# 03_mcu.net
KiCad netlist of a schematic drawn in Altium Designer
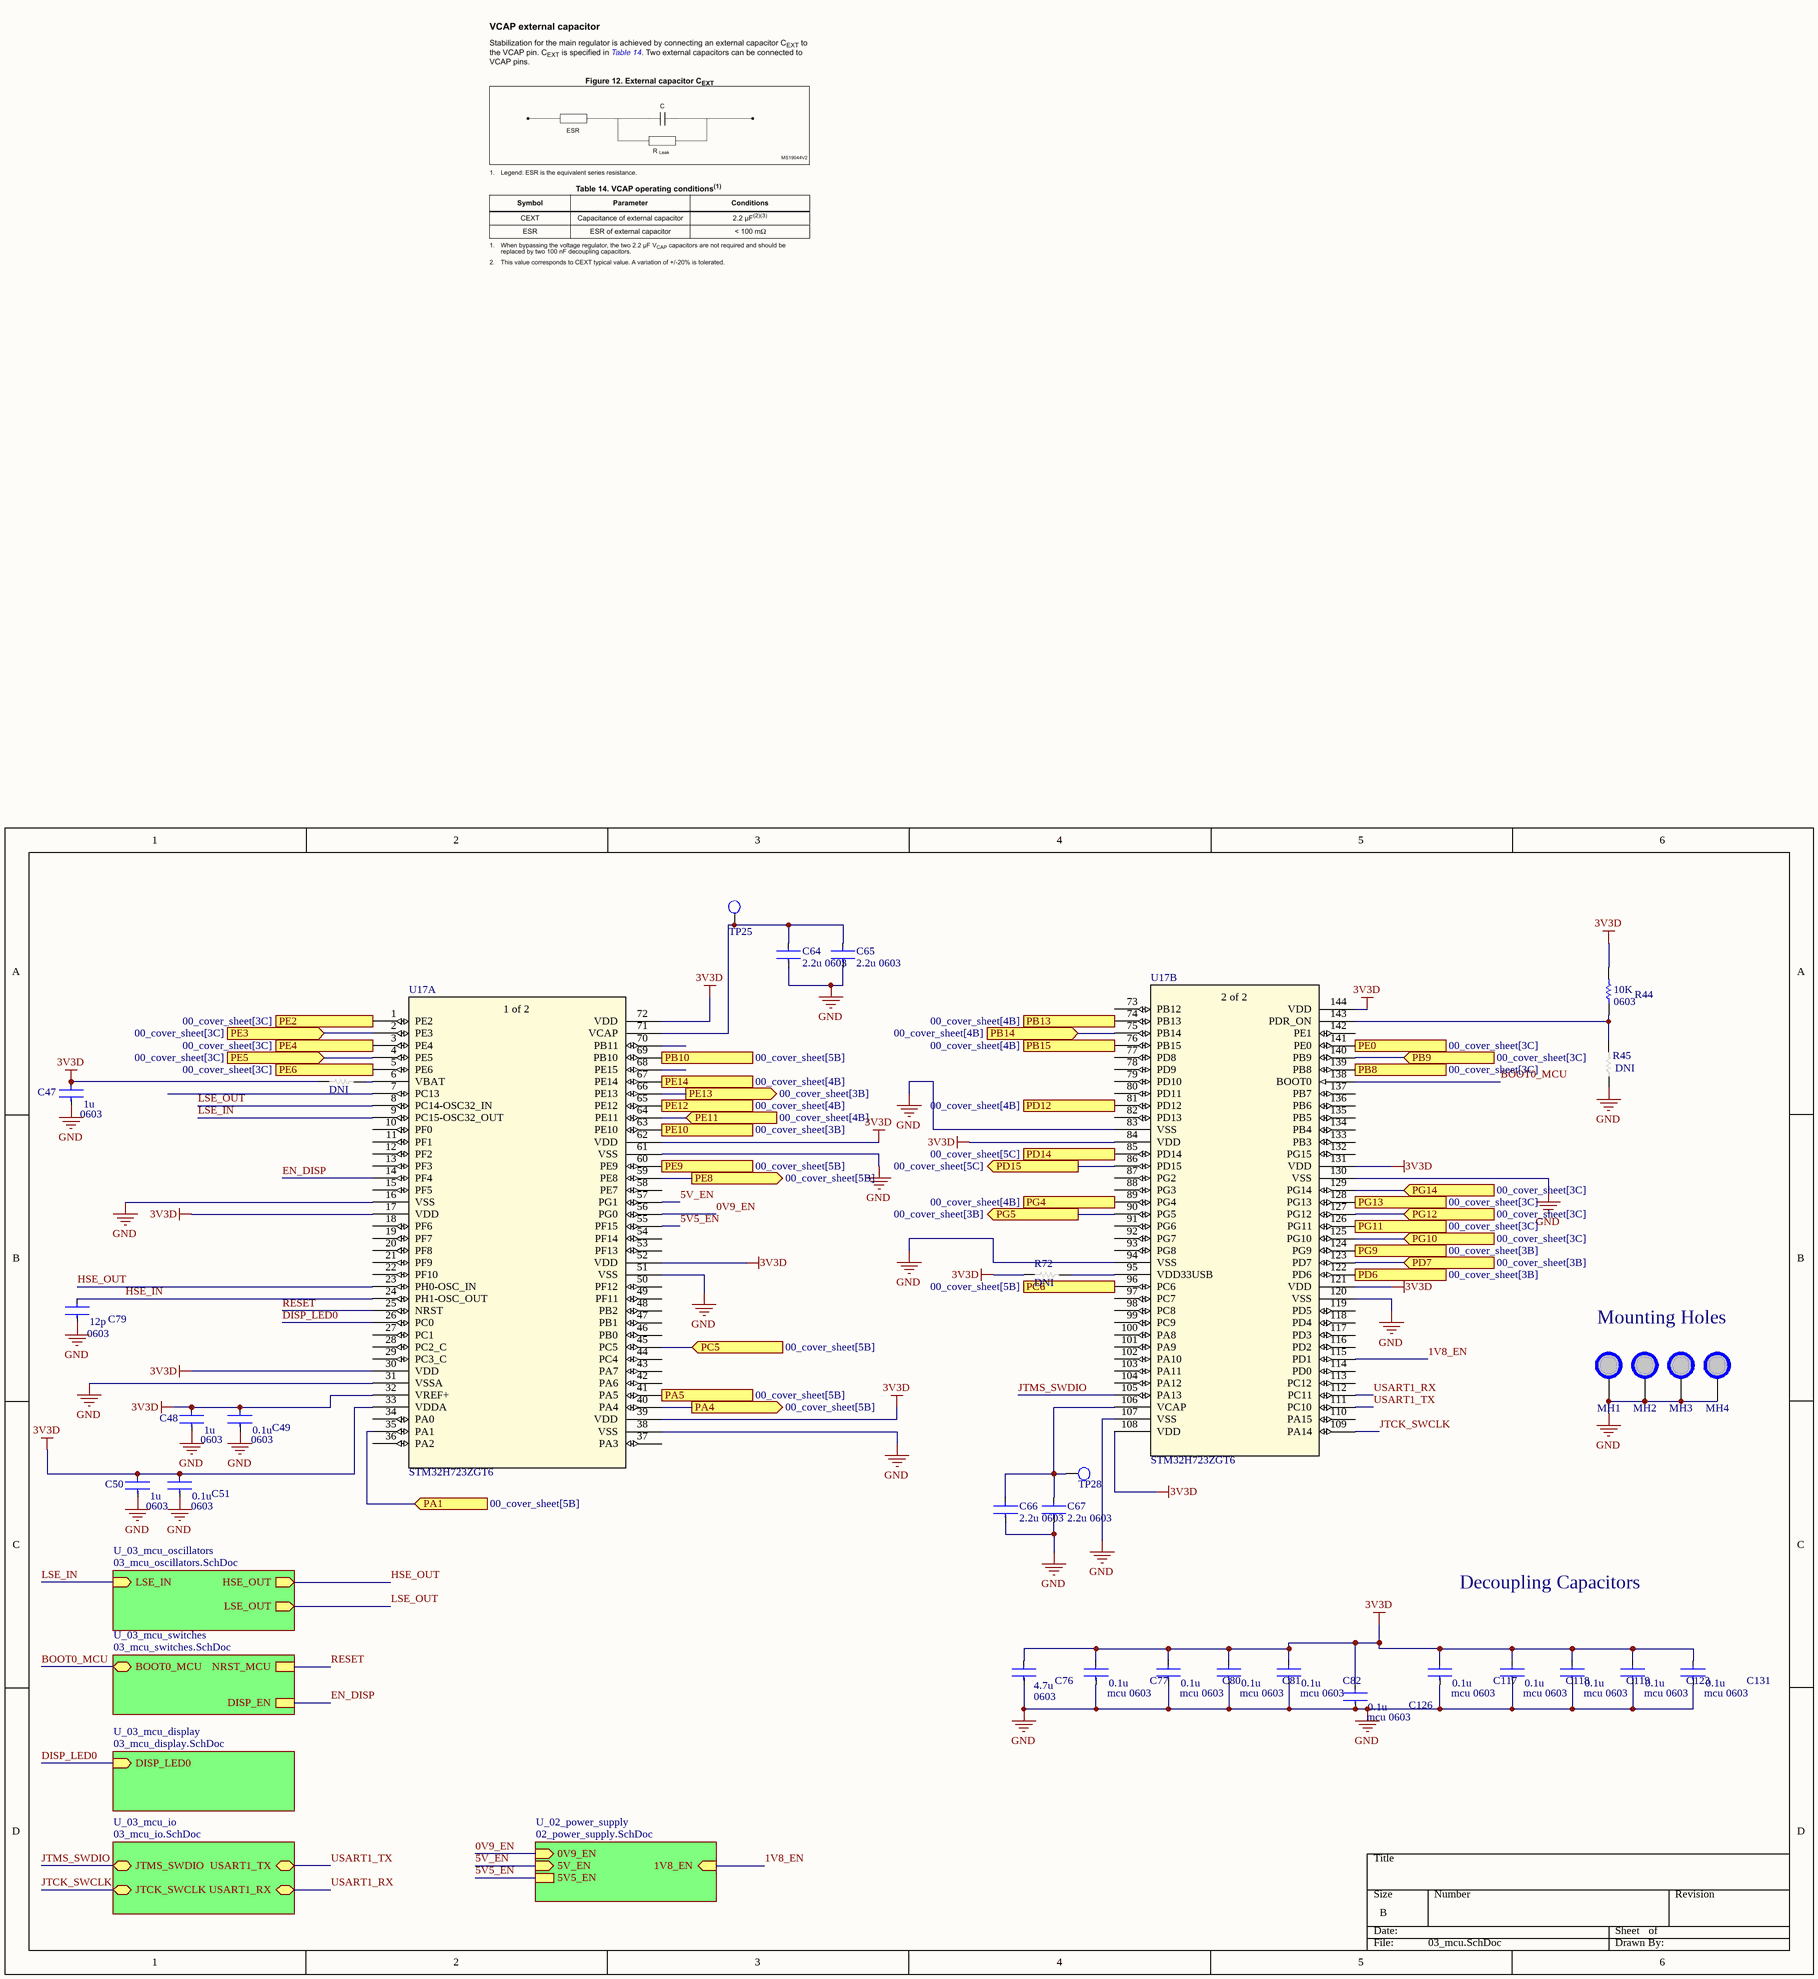
[diagram p0: 03_mcu.SchDoc]

(export (version "E")
  (design (tool "Eeschema 10.0.6"))
  (components
    (comp (ref "C47")
      (value "C1608X5R1E105K080AC")
      (footprint "CAPTDK0603")
      (description "CAP CER 1UF 25V X5R 0603")
      (libsource (lib "tcspc00") (part "C1608X5R1E105K080AC"))
    )
    (comp (ref "C48")
      (value "C1608X5R1E105K080AC")
      (footprint "CAPTDK0603")
      (description "CAP CER 1UF 25V X5R 0603")
      (libsource (lib "tcspc00") (part "C1608X5R1E105K080AC"))
    )
    (comp (ref "C49")
      (value "CGA3E2X7R1H104K080AA")
      (footprint "CAPTDK0603")
      (description "CAP CER 0.1UF 50V X7R 0603")
      (libsource (lib "tcspc00") (part "CGA3E2X7R1H104K080AA"))
    )
    (comp (ref "C50")
      (value "C1608X5R1E105K080AC")
      (footprint "CAPTDK0603")
      (description "CAP CER 1UF 25V X5R 0603")
      (libsource (lib "tcspc00") (part "C1608X5R1E105K080AC"))
    )
    (comp (ref "C51")
      (value "CGA3E2X7R1H104K080AA")
      (footprint "CAPTDK0603")
      (description "CAP CER 0.1UF 50V X7R 0603")
      (libsource (lib "tcspc00") (part "CGA3E2X7R1H104K080AA"))
    )
    (comp (ref "C64")
      (value "2.2u 0603")
      (footprint "CAPTDK0603")
      (description "CAP CER 2.2UF 25V X5R 0603")
      (libsource (lib "tcspc00") (part "C1608X5R1E225K080AB"))
    )
    (comp (ref "C65")
      (value "2.2u 0603")
      (footprint "CAPTDK0603")
      (description "CAP CER 2.2UF 25V X5R 0603")
      (libsource (lib "tcspc00") (part "C1608X5R1E225K080AB"))
    )
    (comp (ref "C66")
      (value "2.2u 0603")
      (footprint "CAPTDK0603")
      (description "CAP CER 2.2UF 25V X5R 0603")
      (libsource (lib "tcspc00") (part "C1608X5R1E225K080AB"))
    )
    (comp (ref "C67")
      (value "2.2u 0603")
      (footprint "CAPTDK0603")
      (description "CAP CER 2.2UF 25V X5R 0603")
      (libsource (lib "tcspc00") (part "C1608X5R1E225K080AB"))
    )
    (comp (ref "C76")
      (value "C1608X5R1E475K080AC")
      (footprint "CAPTDK0603")
      (description "CAP CER 4.7UF 25V X5R 0603")
      (libsource (lib "tcspc00") (part "C1608X5R1E475K080AC"))
    )
    (comp (ref "C77")
      (value "NMC0603X7R104K50TRPF")
      (footprint "CAPTDK0603")
      (description "0.1 µF ±10% 50V Ceramic Capacitor X7R 0603 (1608 Metric) low esr mcu caps")
      (libsource (lib "tcspc00") (part "NMC0603X7R104K50TRPF"))
    )
    (comp (ref "C79")
      (value "CGA3E2C0G1H120J080AA")
      (footprint "CAPTDK0603")
      (description "CAP CER 12PF 50V C0G 0603")
      (libsource (lib "tcspc00") (part "CGA3E2C0G1H120J080AA"))
    )
    (comp (ref "C80")
      (value "NMC0603X7R104K50TRPF")
      (footprint "CAPTDK0603")
      (description "0.1 µF ±10% 50V Ceramic Capacitor X7R 0603 (1608 Metric) low esr mcu caps")
      (libsource (lib "tcspc00") (part "NMC0603X7R104K50TRPF"))
    )
    (comp (ref "C81")
      (value "NMC0603X7R104K50TRPF")
      (footprint "CAPTDK0603")
      (description "0.1 µF ±10% 50V Ceramic Capacitor X7R 0603 (1608 Metric) low esr mcu caps")
      (libsource (lib "tcspc00") (part "NMC0603X7R104K50TRPF"))
    )
    (comp (ref "C82")
      (value "NMC0603X7R104K50TRPF")
      (footprint "CAPTDK0603")
      (description "0.1 µF ±10% 50V Ceramic Capacitor X7R 0603 (1608 Metric) low esr mcu caps")
      (libsource (lib "tcspc00") (part "NMC0603X7R104K50TRPF"))
    )
    (comp (ref "C117")
      (value "NMC0603X7R104K50TRPF")
      (footprint "CAPTDK0603")
      (description "0.1 µF ±10% 50V Ceramic Capacitor X7R 0603 (1608 Metric) low esr mcu caps")
      (libsource (lib "tcspc00") (part "NMC0603X7R104K50TRPF"))
    )
    (comp (ref "C118")
      (value "NMC0603X7R104K50TRPF")
      (footprint "CAPTDK0603")
      (description "0.1 µF ±10% 50V Ceramic Capacitor X7R 0603 (1608 Metric) low esr mcu caps")
      (libsource (lib "tcspc00") (part "NMC0603X7R104K50TRPF"))
    )
    (comp (ref "C119")
      (value "NMC0603X7R104K50TRPF")
      (footprint "CAPTDK0603")
      (description "0.1 µF ±10% 50V Ceramic Capacitor X7R 0603 (1608 Metric) low esr mcu caps")
      (libsource (lib "tcspc00") (part "NMC0603X7R104K50TRPF"))
    )
    (comp (ref "C123")
      (value "NMC0603X7R104K50TRPF")
      (footprint "CAPTDK0603")
      (description "0.1 µF ±10% 50V Ceramic Capacitor X7R 0603 (1608 Metric) low esr mcu caps")
      (libsource (lib "tcspc00") (part "NMC0603X7R104K50TRPF"))
    )
    (comp (ref "C126")
      (value "NMC0603X7R104K50TRPF")
      (footprint "CAPTDK0603")
      (description "0.1 µF ±10% 50V Ceramic Capacitor X7R 0603 (1608 Metric) low esr mcu caps")
      (libsource (lib "tcspc00") (part "NMC0603X7R104K50TRPF"))
    )
    (comp (ref "C131")
      (value "NMC0603X7R104K50TRPF")
      (footprint "CAPTDK0603")
      (description "0.1 µF ±10% 50V Ceramic Capacitor X7R 0603 (1608 Metric) low esr mcu caps")
      (libsource (lib "tcspc00") (part "NMC0603X7R104K50TRPF"))
    )
    (comp (ref "MH1")
      (value "M3.5 Mounting Hole")
      (footprint "M3.5 Mounting Hole - Supported")
      (fields (field (name "PUBLISHER") "Altium Limited"))
      (libsource (lib "tcspc00") (part "M3.5 Mounting Hole"))
    )
    (comp (ref "MH2")
      (value "M3.5 Mounting Hole")
      (footprint "M3.5 Mounting Hole - Supported")
      (fields (field (name "PUBLISHER") "Altium Limited"))
      (libsource (lib "tcspc00") (part "M3.5 Mounting Hole"))
    )
    (comp (ref "MH3")
      (value "M3.5 Mounting Hole")
      (footprint "M3.5 Mounting Hole - Supported")
      (fields (field (name "PUBLISHER") "Altium Limited"))
      (libsource (lib "tcspc00") (part "M3.5 Mounting Hole"))
    )
    (comp (ref "MH4")
      (value "M3.5 Mounting Hole")
      (footprint "M3.5 Mounting Hole - Supported")
      (fields (field (name "PUBLISHER") "Altium Limited"))
      (libsource (lib "tcspc00") (part "M3.5 Mounting Hole"))
    )
    (comp (ref "R44")
      (value "RMCF0603JG10K0")
      (footprint "RES-STACK-POLE-0603")
      (description "RES 10K OHM 5% 1/10W 0603")
      (libsource (lib "tcspc00") (part "RMCF0603JG10K0"))
    )
    (comp (ref "R45")
      (value "DNI")
      (footprint "RES_0603")
      (description "RES DNI 0603")
      (libsource (lib "tcspc00") (part "R0603"))
    )
    (comp (ref "R46")
      (value "DNI")
      (footprint "RES_0603")
      (description "RES DNI 0603")
      (libsource (lib "tcspc00") (part "R0603"))
    )
    (comp (ref "R72")
      (value "DNI")
      (footprint "RES_0603")
      (description "RES DNI 0603")
      (libsource (lib "tcspc00") (part "R0603"))
    )
    (comp (ref "TP25")
      (value "TESTPOINT_S")
      (footprint "TESTPOINT_S")
      (description "Testpoint Surface Pad")
      (libsource (lib "Schlib1") (part "TESTPOINT_S"))
    )
    (comp (ref "TP28")
      (value "TESTPOINT_S")
      (footprint "TESTPOINT_S")
      (description "Testpoint Surface Pad")
      (libsource (lib "Schlib1") (part "TESTPOINT_S"))
    )
    (comp (ref "U17")
      (value "STM32H723ZGT6")
      (footprint "LQFP144")
      (description "No Description Available")
      (fields (field (name "COPYRIGHT") "Copyright (C) 2024 Ultra Librarian. All rights reserved."))
      (libsource (lib "tcspc00") (part "STM32H723ZGT6"))
    )
  )
  (nets
    (net (code "1") (name "/0V9_EN") (class "Default")
      (node (ref "U17") (pin "56") (pinfunction "PG0_56") (pintype "bidirectional"))
    )
    (net (code "2") (name "/1V8_EN") (class "Default")
      (node (ref "U17") (pin "115") (pinfunction "PD1_115") (pintype "bidirectional"))
    )
    (net (code "3") (name "/5V5_EN") (class "Default")
      (node (ref "U17") (pin "55") (pinfunction "PF15_55") (pintype "bidirectional"))
    )
    (net (code "4") (name "/5V_EN") (class "Default")
      (node (ref "U17") (pin "57") (pinfunction "PG1_57") (pintype "bidirectional"))
    )
    (net (code "5") (name "/BOOT0_MCU") (class "Default")
      (node (ref "U17") (pin "138") (pinfunction "BOOT0_138") (pintype "input"))
    )
    (net (code "6") (name "/DISP_LED0") (class "Default")
      (node (ref "U17") (pin "26") (pinfunction "PC0_26") (pintype "bidirectional"))
    )
    (net (code "7") (name "/EN_DISP") (class "Default")
      (node (ref "U17") (pin "14") (pinfunction "PF4_14") (pintype "bidirectional"))
    )
    (net (code "8") (name "/HSE_IN") (class "Default")
      (node (ref "C79") (pin "1") (pinfunction "1_1") (pintype "passive"))
      (node (ref "U17") (pin "24") (pinfunction "PH1-OSC_OUT_24") (pintype "bidirectional"))
    )
    (net (code "9") (name "/HSE_OUT") (class "Default")
      (node (ref "U17") (pin "23") (pinfunction "PH0-OSC_IN_23") (pintype "bidirectional"))
    )
    (net (code "10") (name "/JTCK_SWCLK") (class "Default")
      (node (ref "U17") (pin "109") (pinfunction "PA14_109") (pintype "bidirectional"))
    )
    (net (code "11") (name "/JTMS_SWDIO") (class "Default")
      (node (ref "U17") (pin "105") (pinfunction "PA13_105") (pintype "bidirectional"))
    )
    (net (code "12") (name "/LSE_IN") (class "Default")
      (node (ref "U17") (pin "9") (pinfunction "PC15-OSC32_OUT_9") (pintype "bidirectional"))
    )
    (net (code "13") (name "/LSE_OUT") (class "Default")
      (node (ref "U17") (pin "8") (pinfunction "PC14-OSC32_IN_8") (pintype "bidirectional"))
    )
    (net (code "14") (name "/PA1") (class "Default")
      (node (ref "U17") (pin "35") (pinfunction "PA1_35") (pintype "bidirectional"))
    )
    (net (code "15") (name "/PA4") (class "Default")
      (node (ref "U17") (pin "40") (pinfunction "PA4_40") (pintype "bidirectional"))
    )
    (net (code "16") (name "/PA5") (class "Default")
      (node (ref "U17") (pin "41") (pinfunction "PA5_41") (pintype "bidirectional"))
    )
    (net (code "17") (name "/PB8") (class "Default")
      (node (ref "U17") (pin "139") (pinfunction "PB8_139") (pintype "bidirectional"))
    )
    (net (code "18") (name "/PB9") (class "Default")
      (node (ref "U17") (pin "140") (pinfunction "PB9_140") (pintype "bidirectional"))
    )
    (net (code "19") (name "/PB10") (class "Default")
      (node (ref "U17") (pin "69") (pinfunction "PB10_69") (pintype "bidirectional"))
    )
    (net (code "20") (name "/PB13") (class "Default")
      (node (ref "U17") (pin "74") (pinfunction "PB13_74") (pintype "bidirectional"))
    )
    (net (code "21") (name "/PB14") (class "Default")
      (node (ref "U17") (pin "75") (pinfunction "PB14_75") (pintype "bidirectional"))
    )
    (net (code "22") (name "/PB15") (class "Default")
      (node (ref "U17") (pin "76") (pinfunction "PB15_76") (pintype "bidirectional"))
    )
    (net (code "23") (name "/PC5") (class "Default")
      (node (ref "U17") (pin "45") (pinfunction "PC5_45") (pintype "bidirectional"))
    )
    (net (code "24") (name "/PC6") (class "Default")
      (node (ref "U17") (pin "96") (pinfunction "PC6_96") (pintype "bidirectional"))
    )
    (net (code "25") (name "/PD6") (class "Default")
      (node (ref "U17") (pin "122") (pinfunction "PD6_122") (pintype "bidirectional"))
    )
    (net (code "26") (name "/PD7") (class "Default")
      (node (ref "U17") (pin "123") (pinfunction "PD7_123") (pintype "bidirectional"))
    )
    (net (code "27") (name "/PD12") (class "Default")
      (node (ref "U17") (pin "81") (pinfunction "PD12_81") (pintype "bidirectional"))
    )
    (net (code "28") (name "/PD14") (class "Default")
      (node (ref "U17") (pin "85") (pinfunction "PD14_85") (pintype "bidirectional"))
    )
    (net (code "29") (name "/PD15") (class "Default")
      (node (ref "U17") (pin "86") (pinfunction "PD15_86") (pintype "bidirectional"))
    )
    (net (code "30") (name "/PE0") (class "Default")
      (node (ref "U17") (pin "141") (pinfunction "PE0_141") (pintype "bidirectional"))
    )
    (net (code "31") (name "/PE2") (class "Default")
      (node (ref "U17") (pin "1") (pinfunction "PE2_1") (pintype "bidirectional"))
    )
    (net (code "32") (name "/PE3") (class "Default")
      (node (ref "U17") (pin "2") (pinfunction "PE3_2") (pintype "bidirectional"))
    )
    (net (code "33") (name "/PE4") (class "Default")
      (node (ref "U17") (pin "3") (pinfunction "PE4_3") (pintype "bidirectional"))
    )
    (net (code "34") (name "/PE5") (class "Default")
      (node (ref "U17") (pin "4") (pinfunction "PE5_4") (pintype "bidirectional"))
    )
    (net (code "35") (name "/PE6") (class "Default")
      (node (ref "U17") (pin "5") (pinfunction "PE6_5") (pintype "bidirectional"))
    )
    (net (code "36") (name "/PE8") (class "Default")
      (node (ref "U17") (pin "59") (pinfunction "PE8_59") (pintype "bidirectional"))
    )
    (net (code "37") (name "/PE9") (class "Default")
      (node (ref "U17") (pin "60") (pinfunction "PE9_60") (pintype "bidirectional"))
    )
    (net (code "38") (name "/PE10") (class "Default")
      (node (ref "U17") (pin "63") (pinfunction "PE10_63") (pintype "bidirectional"))
    )
    (net (code "39") (name "/PE11") (class "Default")
      (node (ref "U17") (pin "64") (pinfunction "PE11_64") (pintype "bidirectional"))
    )
    (net (code "40") (name "/PE12") (class "Default")
      (node (ref "U17") (pin "65") (pinfunction "PE12_65") (pintype "bidirectional"))
    )
    (net (code "41") (name "/PE13") (class "Default")
      (node (ref "U17") (pin "66") (pinfunction "PE13_66") (pintype "bidirectional"))
    )
    (net (code "42") (name "/PE14") (class "Default")
      (node (ref "U17") (pin "67") (pinfunction "PE14_67") (pintype "bidirectional"))
    )
    (net (code "43") (name "/PG4") (class "Default")
      (node (ref "U17") (pin "89") (pinfunction "PG4_89") (pintype "bidirectional"))
    )
    (net (code "44") (name "/PG5") (class "Default")
      (node (ref "U17") (pin "90") (pinfunction "PG5_90") (pintype "bidirectional"))
    )
    (net (code "45") (name "/PG9") (class "Default")
      (node (ref "U17") (pin "124") (pinfunction "PG9_124") (pintype "bidirectional"))
    )
    (net (code "46") (name "/PG10") (class "Default")
      (node (ref "U17") (pin "125") (pinfunction "PG10_125") (pintype "bidirectional"))
    )
    (net (code "47") (name "/PG11") (class "Default")
      (node (ref "U17") (pin "126") (pinfunction "PG11_126") (pintype "bidirectional"))
    )
    (net (code "48") (name "/PG12") (class "Default")
      (node (ref "U17") (pin "127") (pinfunction "PG12_127") (pintype "bidirectional"))
    )
    (net (code "49") (name "/PG13") (class "Default")
      (node (ref "U17") (pin "128") (pinfunction "PG13_128") (pintype "bidirectional"))
    )
    (net (code "50") (name "/PG14") (class "Default")
      (node (ref "U17") (pin "129") (pinfunction "PG14_129") (pintype "bidirectional"))
    )
    (net (code "51") (name "/RESET") (class "Default")
      (node (ref "U17") (pin "25") (pinfunction "NRST_25") (pintype "bidirectional"))
    )
    (net (code "52") (name "/USART1_RX") (class "Default")
      (node (ref "U17") (pin "112") (pinfunction "PC11_112") (pintype "bidirectional"))
    )
    (net (code "53") (name "/USART1_TX") (class "Default")
      (node (ref "U17") (pin "111") (pinfunction "PC10_111") (pintype "bidirectional"))
    )
    (net (code "54") (name "3V3D") (class "Default")
      (node (ref "C117") (pin "1") (pinfunction "1_1") (pintype "passive"))
      (node (ref "C118") (pin "1") (pinfunction "1_1") (pintype "passive"))
      (node (ref "C119") (pin "1") (pinfunction "1_1") (pintype "passive"))
      (node (ref "C123") (pin "1") (pinfunction "1_1") (pintype "passive"))
      (node (ref "C126") (pin "1") (pinfunction "1_1") (pintype "passive"))
      (node (ref "C131") (pin "1") (pinfunction "1_1") (pintype "passive"))
      (node (ref "C47") (pin "1") (pinfunction "1_1") (pintype "passive"))
      (node (ref "C48") (pin "1") (pinfunction "1_1") (pintype "passive"))
      (node (ref "C49") (pin "1") (pinfunction "1_1") (pintype "passive"))
      (node (ref "C50") (pin "1") (pinfunction "1_1") (pintype "passive"))
      (node (ref "C51") (pin "1") (pinfunction "1_1") (pintype "passive"))
      (node (ref "C76") (pin "1") (pinfunction "1_1") (pintype "passive"))
      (node (ref "C77") (pin "1") (pinfunction "1_1") (pintype "passive"))
      (node (ref "C80") (pin "1") (pinfunction "1_1") (pintype "passive"))
      (node (ref "C81") (pin "1") (pinfunction "1_1") (pintype "passive"))
      (node (ref "C82") (pin "1") (pinfunction "1_1") (pintype "passive"))
      (node (ref "R44") (pin "2") (pinfunction "2_2") (pintype "passive"))
      (node (ref "R46") (pin "1") (pinfunction "1_1") (pintype "passive"))
      (node (ref "R72") (pin "1") (pinfunction "1_1") (pintype "passive"))
      (node (ref "U17") (pin "108") (pinfunction "VDD_108") (pintype "power_in"))
      (node (ref "U17") (pin "121") (pinfunction "VDD_121") (pintype "power_in"))
      (node (ref "U17") (pin "131") (pinfunction "VDD_131") (pintype "power_in"))
      (node (ref "U17") (pin "144") (pinfunction "VDD_144") (pintype "power_in"))
      (node (ref "U17") (pin "17") (pinfunction "VDD_17") (pintype "power_in"))
      (node (ref "U17") (pin "30") (pinfunction "VDD_30") (pintype "power_in"))
      (node (ref "U17") (pin "32") (pinfunction "VREF+_32") (pintype "power_in"))
      (node (ref "U17") (pin "33") (pinfunction "VDDA_33") (pintype "power_in"))
      (node (ref "U17") (pin "39") (pinfunction "VDD_39") (pintype "power_in"))
      (node (ref "U17") (pin "52") (pinfunction "VDD_52") (pintype "power_in"))
      (node (ref "U17") (pin "62") (pinfunction "VDD_62") (pintype "power_in"))
      (node (ref "U17") (pin "72") (pinfunction "VDD_72") (pintype "power_in"))
      (node (ref "U17") (pin "84") (pinfunction "VDD_84") (pintype "power_in"))
    )
    (net (code "55") (name "GND") (class "Default")
      (node (ref "C117") (pin "2") (pinfunction "2_2") (pintype "passive"))
      (node (ref "C118") (pin "2") (pinfunction "2_2") (pintype "passive"))
      (node (ref "C119") (pin "2") (pinfunction "2_2") (pintype "passive"))
      (node (ref "C123") (pin "2") (pinfunction "2_2") (pintype "passive"))
      (node (ref "C126") (pin "2") (pinfunction "2_2") (pintype "passive"))
      (node (ref "C131") (pin "2") (pinfunction "2_2") (pintype "passive"))
      (node (ref "C47") (pin "2") (pinfunction "2_2") (pintype "passive"))
      (node (ref "C48") (pin "2") (pinfunction "2_2") (pintype "passive"))
      (node (ref "C49") (pin "2") (pinfunction "2_2") (pintype "passive"))
      (node (ref "C50") (pin "2") (pinfunction "2_2") (pintype "passive"))
      (node (ref "C51") (pin "2") (pinfunction "2_2") (pintype "passive"))
      (node (ref "C64") (pin "2") (pinfunction "2_2") (pintype "passive"))
      (node (ref "C65") (pin "2") (pinfunction "2_2") (pintype "passive"))
      (node (ref "C66") (pin "2") (pinfunction "2_2") (pintype "passive"))
      (node (ref "C67") (pin "2") (pinfunction "2_2") (pintype "passive"))
      (node (ref "C76") (pin "2") (pinfunction "2_2") (pintype "passive"))
      (node (ref "C77") (pin "2") (pinfunction "2_2") (pintype "passive"))
      (node (ref "C79") (pin "2") (pinfunction "2_2") (pintype "passive"))
      (node (ref "C80") (pin "2") (pinfunction "2_2") (pintype "passive"))
      (node (ref "C81") (pin "2") (pinfunction "2_2") (pintype "passive"))
      (node (ref "C82") (pin "2") (pinfunction "2_2") (pintype "passive"))
      (node (ref "MH1") (pin "1") (pinfunction "1_1") (pintype "passive"))
      (node (ref "MH2") (pin "1") (pinfunction "1_1") (pintype "passive"))
      (node (ref "MH3") (pin "1") (pinfunction "1_1") (pintype "passive"))
      (node (ref "MH4") (pin "1") (pinfunction "1_1") (pintype "passive"))
      (node (ref "R45") (pin "1") (pinfunction "1_1") (pintype "passive"))
      (node (ref "U17") (pin "107") (pinfunction "VSS_107") (pintype "power_in"))
      (node (ref "U17") (pin "120") (pinfunction "VSS_120") (pintype "power_in"))
      (node (ref "U17") (pin "130") (pinfunction "VSS_130") (pintype "power_in"))
      (node (ref "U17") (pin "16") (pinfunction "VSS_16") (pintype "power_in"))
      (node (ref "U17") (pin "31") (pinfunction "VSSA_31") (pintype "power_in"))
      (node (ref "U17") (pin "38") (pinfunction "VSS_38") (pintype "power_in"))
      (node (ref "U17") (pin "51") (pinfunction "VSS_51") (pintype "power_in"))
      (node (ref "U17") (pin "61") (pinfunction "VSS_61") (pintype "power_in"))
      (node (ref "U17") (pin "83") (pinfunction "VSS_83") (pintype "power_in"))
      (node (ref "U17") (pin "94") (pinfunction "VSS_94") (pintype "power_in"))
    )
    (net (code "56") (name "Net-(U17A-VBAT)") (class "Default")
      (node (ref "R46") (pin "2") (pinfunction "2_2") (pintype "passive"))
      (node (ref "U17") (pin "6") (pinfunction "VBAT_6") (pintype "power_in"))
    )
    (net (code "57") (name "Net-(U17A-VCAP)") (class "Default")
      (node (ref "C64") (pin "1") (pinfunction "1_1") (pintype "passive"))
      (node (ref "C65") (pin "1") (pinfunction "1_1") (pintype "passive"))
      (node (ref "TP25") (pin "1") (pinfunction "1_1") (pintype "passive"))
      (node (ref "U17") (pin "71") (pinfunction "VCAP_71") (pintype "power_in"))
    )
    (net (code "58") (name "Net-(U17B-PDR_ON)") (class "Default")
      (node (ref "R44") (pin "1") (pinfunction "1_1") (pintype "passive"))
      (node (ref "R45") (pin "2") (pinfunction "2_2") (pintype "passive"))
      (node (ref "U17") (pin "143") (pinfunction "PDR_ON_143") (pintype "power_in"))
    )
    (net (code "59") (name "Net-(U17B-VCAP)") (class "Default")
      (node (ref "C66") (pin "1") (pinfunction "1_1") (pintype "passive"))
      (node (ref "C67") (pin "1") (pinfunction "1_1") (pintype "passive"))
      (node (ref "TP28") (pin "1") (pinfunction "1_1") (pintype "passive"))
      (node (ref "U17") (pin "106") (pinfunction "VCAP_106") (pintype "power_in"))
    )
    (net (code "60") (name "Net-(U17B-VDD33USB)") (class "Default")
      (node (ref "R72") (pin "2") (pinfunction "2_2") (pintype "passive"))
      (node (ref "U17") (pin "95") (pinfunction "VDD33USB_95") (pintype "power_in"))
    )
    (net (code "61") (name "unconnected-(U17A-PA0-Pad34)") (class "Default")
      (node (ref "U17") (pin "34") (pinfunction "PA0_34") (pintype "bidirectional"))
    )
    (net (code "62") (name "unconnected-(U17A-PA2-Pad36)") (class "Default")
      (node (ref "U17") (pin "36") (pinfunction "PA2_36") (pintype "bidirectional"))
    )
    (net (code "63") (name "unconnected-(U17A-PA3-Pad37)") (class "Default")
      (node (ref "U17") (pin "37") (pinfunction "PA3_37") (pintype "bidirectional"))
    )
    (net (code "64") (name "unconnected-(U17A-PA6-Pad42)") (class "Default")
      (node (ref "U17") (pin "42") (pinfunction "PA6_42") (pintype "bidirectional"))
    )
    (net (code "65") (name "unconnected-(U17A-PA7-Pad43)") (class "Default")
      (node (ref "U17") (pin "43") (pinfunction "PA7_43") (pintype "bidirectional"))
    )
    (net (code "66") (name "unconnected-(U17A-PB0-Pad46)") (class "Default")
      (node (ref "U17") (pin "46") (pinfunction "PB0_46") (pintype "bidirectional"))
    )
    (net (code "67") (name "unconnected-(U17A-PB1-Pad47)") (class "Default")
      (node (ref "U17") (pin "47") (pinfunction "PB1_47") (pintype "bidirectional"))
    )
    (net (code "68") (name "unconnected-(U17A-PB2-Pad48)") (class "Default")
      (node (ref "U17") (pin "48") (pinfunction "PB2_48") (pintype "bidirectional"))
    )
    (net (code "69") (name "unconnected-(U17A-PB11-Pad70)") (class "Default")
      (node (ref "U17") (pin "70") (pinfunction "PB11_70") (pintype "bidirectional"))
    )
    (net (code "70") (name "unconnected-(U17A-PC1-Pad27)") (class "Default")
      (node (ref "U17") (pin "27") (pinfunction "PC1_27") (pintype "bidirectional"))
    )
    (net (code "71") (name "unconnected-(U17A-PC2_C-Pad28)") (class "Default")
      (node (ref "U17") (pin "28") (pinfunction "PC2_C_28") (pintype "bidirectional"))
    )
    (net (code "72") (name "unconnected-(U17A-PC3_C-Pad29)") (class "Default")
      (node (ref "U17") (pin "29") (pinfunction "PC3_C_29") (pintype "bidirectional"))
    )
    (net (code "73") (name "unconnected-(U17A-PC4-Pad44)") (class "Default")
      (node (ref "U17") (pin "44") (pinfunction "PC4_44") (pintype "bidirectional"))
    )
    (net (code "74") (name "unconnected-(U17A-PC13-Pad7)") (class "Default")
      (node (ref "U17") (pin "7") (pinfunction "PC13_7") (pintype "bidirectional"))
    )
    (net (code "75") (name "unconnected-(U17A-PE7-Pad58)") (class "Default")
      (node (ref "U17") (pin "58") (pinfunction "PE7_58") (pintype "bidirectional"))
    )
    (net (code "76") (name "unconnected-(U17A-PE15-Pad68)") (class "Default")
      (node (ref "U17") (pin "68") (pinfunction "PE15_68") (pintype "bidirectional"))
    )
    (net (code "77") (name "unconnected-(U17A-PF0-Pad10)") (class "Default")
      (node (ref "U17") (pin "10") (pinfunction "PF0_10") (pintype "bidirectional"))
    )
    (net (code "78") (name "unconnected-(U17A-PF1-Pad11)") (class "Default")
      (node (ref "U17") (pin "11") (pinfunction "PF1_11") (pintype "bidirectional"))
    )
    (net (code "79") (name "unconnected-(U17A-PF2-Pad12)") (class "Default")
      (node (ref "U17") (pin "12") (pinfunction "PF2_12") (pintype "bidirectional"))
    )
    (net (code "80") (name "unconnected-(U17A-PF3-Pad13)") (class "Default")
      (node (ref "U17") (pin "13") (pinfunction "PF3_13") (pintype "bidirectional"))
    )
    (net (code "81") (name "unconnected-(U17A-PF5-Pad15)") (class "Default")
      (node (ref "U17") (pin "15") (pinfunction "PF5_15") (pintype "bidirectional"))
    )
    (net (code "82") (name "unconnected-(U17A-PF6-Pad18)") (class "Default")
      (node (ref "U17") (pin "18") (pinfunction "PF6_18") (pintype "bidirectional"))
    )
    (net (code "83") (name "unconnected-(U17A-PF7-Pad19)") (class "Default")
      (node (ref "U17") (pin "19") (pinfunction "PF7_19") (pintype "bidirectional"))
    )
    (net (code "84") (name "unconnected-(U17A-PF8-Pad20)") (class "Default")
      (node (ref "U17") (pin "20") (pinfunction "PF8_20") (pintype "bidirectional"))
    )
    (net (code "85") (name "unconnected-(U17A-PF9-Pad21)") (class "Default")
      (node (ref "U17") (pin "21") (pinfunction "PF9_21") (pintype "bidirectional"))
    )
    (net (code "86") (name "unconnected-(U17A-PF10-Pad22)") (class "Default")
      (node (ref "U17") (pin "22") (pinfunction "PF10_22") (pintype "bidirectional"))
    )
    (net (code "87") (name "unconnected-(U17A-PF11-Pad49)") (class "Default")
      (node (ref "U17") (pin "49") (pinfunction "PF11_49") (pintype "bidirectional"))
    )
    (net (code "88") (name "unconnected-(U17A-PF12-Pad50)") (class "Default")
      (node (ref "U17") (pin "50") (pinfunction "PF12_50") (pintype "bidirectional"))
    )
    (net (code "89") (name "unconnected-(U17A-PF13-Pad53)") (class "Default")
      (node (ref "U17") (pin "53") (pinfunction "PF13_53") (pintype "bidirectional"))
    )
    (net (code "90") (name "unconnected-(U17A-PF14-Pad54)") (class "Default")
      (node (ref "U17") (pin "54") (pinfunction "PF14_54") (pintype "bidirectional"))
    )
    (net (code "91") (name "unconnected-(U17B-PA8-Pad100)") (class "Default")
      (node (ref "U17") (pin "100") (pinfunction "PA8_100") (pintype "bidirectional"))
    )
    (net (code "92") (name "unconnected-(U17B-PA9-Pad101)") (class "Default")
      (node (ref "U17") (pin "101") (pinfunction "PA9_101") (pintype "bidirectional"))
    )
    (net (code "93") (name "unconnected-(U17B-PA10-Pad102)") (class "Default")
      (node (ref "U17") (pin "102") (pinfunction "PA10_102") (pintype "bidirectional"))
    )
    (net (code "94") (name "unconnected-(U17B-PA11-Pad103)") (class "Default")
      (node (ref "U17") (pin "103") (pinfunction "PA11_103") (pintype "bidirectional"))
    )
    (net (code "95") (name "unconnected-(U17B-PA12-Pad104)") (class "Default")
      (node (ref "U17") (pin "104") (pinfunction "PA12_104") (pintype "bidirectional"))
    )
    (net (code "96") (name "unconnected-(U17B-PA15-Pad110)") (class "Default")
      (node (ref "U17") (pin "110") (pinfunction "PA15_110") (pintype "bidirectional"))
    )
    (net (code "97") (name "unconnected-(U17B-PB3-Pad133)") (class "Default")
      (node (ref "U17") (pin "133") (pinfunction "PB3_133") (pintype "bidirectional"))
    )
    (net (code "98") (name "unconnected-(U17B-PB4-Pad134)") (class "Default")
      (node (ref "U17") (pin "134") (pinfunction "PB4_134") (pintype "bidirectional"))
    )
    (net (code "99") (name "unconnected-(U17B-PB5-Pad135)") (class "Default")
      (node (ref "U17") (pin "135") (pinfunction "PB5_135") (pintype "bidirectional"))
    )
    (net (code "100") (name "unconnected-(U17B-PB6-Pad136)") (class "Default")
      (node (ref "U17") (pin "136") (pinfunction "PB6_136") (pintype "bidirectional"))
    )
    (net (code "101") (name "unconnected-(U17B-PB7-Pad137)") (class "Default")
      (node (ref "U17") (pin "137") (pinfunction "PB7_137") (pintype "bidirectional"))
    )
    (net (code "102") (name "unconnected-(U17B-PB12-Pad73)") (class "Default")
      (node (ref "U17") (pin "73") (pinfunction "PB12_73") (pintype "bidirectional"))
    )
    (net (code "103") (name "unconnected-(U17B-PC7-Pad97)") (class "Default")
      (node (ref "U17") (pin "97") (pinfunction "PC7_97") (pintype "bidirectional"))
    )
    (net (code "104") (name "unconnected-(U17B-PC8-Pad98)") (class "Default")
      (node (ref "U17") (pin "98") (pinfunction "PC8_98") (pintype "bidirectional"))
    )
    (net (code "105") (name "unconnected-(U17B-PC9-Pad99)") (class "Default")
      (node (ref "U17") (pin "99") (pinfunction "PC9_99") (pintype "bidirectional"))
    )
    (net (code "106") (name "unconnected-(U17B-PC12-Pad113)") (class "Default")
      (node (ref "U17") (pin "113") (pinfunction "PC12_113") (pintype "bidirectional"))
    )
    (net (code "107") (name "unconnected-(U17B-PD0-Pad114)") (class "Default")
      (node (ref "U17") (pin "114") (pinfunction "PD0_114") (pintype "bidirectional"))
    )
    (net (code "108") (name "unconnected-(U17B-PD2-Pad116)") (class "Default")
      (node (ref "U17") (pin "116") (pinfunction "PD2_116") (pintype "bidirectional"))
    )
    (net (code "109") (name "unconnected-(U17B-PD3-Pad117)") (class "Default")
      (node (ref "U17") (pin "117") (pinfunction "PD3_117") (pintype "bidirectional"))
    )
    (net (code "110") (name "unconnected-(U17B-PD4-Pad118)") (class "Default")
      (node (ref "U17") (pin "118") (pinfunction "PD4_118") (pintype "bidirectional"))
    )
    (net (code "111") (name "unconnected-(U17B-PD5-Pad119)") (class "Default")
      (node (ref "U17") (pin "119") (pinfunction "PD5_119") (pintype "bidirectional"))
    )
    (net (code "112") (name "unconnected-(U17B-PD8-Pad77)") (class "Default")
      (node (ref "U17") (pin "77") (pinfunction "PD8_77") (pintype "bidirectional"))
    )
    (net (code "113") (name "unconnected-(U17B-PD9-Pad78)") (class "Default")
      (node (ref "U17") (pin "78") (pinfunction "PD9_78") (pintype "bidirectional"))
    )
    (net (code "114") (name "unconnected-(U17B-PD10-Pad79)") (class "Default")
      (node (ref "U17") (pin "79") (pinfunction "PD10_79") (pintype "bidirectional"))
    )
    (net (code "115") (name "unconnected-(U17B-PD11-Pad80)") (class "Default")
      (node (ref "U17") (pin "80") (pinfunction "PD11_80") (pintype "bidirectional"))
    )
    (net (code "116") (name "unconnected-(U17B-PD13-Pad82)") (class "Default")
      (node (ref "U17") (pin "82") (pinfunction "PD13_82") (pintype "bidirectional"))
    )
    (net (code "117") (name "unconnected-(U17B-PE1-Pad142)") (class "Default")
      (node (ref "U17") (pin "142") (pinfunction "PE1_142") (pintype "bidirectional"))
    )
    (net (code "118") (name "unconnected-(U17B-PG2-Pad87)") (class "Default")
      (node (ref "U17") (pin "87") (pinfunction "PG2_87") (pintype "bidirectional"))
    )
    (net (code "119") (name "unconnected-(U17B-PG3-Pad88)") (class "Default")
      (node (ref "U17") (pin "88") (pinfunction "PG3_88") (pintype "bidirectional"))
    )
    (net (code "120") (name "unconnected-(U17B-PG6-Pad91)") (class "Default")
      (node (ref "U17") (pin "91") (pinfunction "PG6_91") (pintype "bidirectional"))
    )
    (net (code "121") (name "unconnected-(U17B-PG7-Pad92)") (class "Default")
      (node (ref "U17") (pin "92") (pinfunction "PG7_92") (pintype "bidirectional"))
    )
    (net (code "122") (name "unconnected-(U17B-PG8-Pad93)") (class "Default")
      (node (ref "U17") (pin "93") (pinfunction "PG8_93") (pintype "bidirectional"))
    )
    (net (code "123") (name "unconnected-(U17B-PG15-Pad132)") (class "Default")
      (node (ref "U17") (pin "132") (pinfunction "PG15_132") (pintype "bidirectional"))
    )
  )
)
